# controlled_rectifier2.net
KiCad netlist of a schematic drawn in Altium Designer
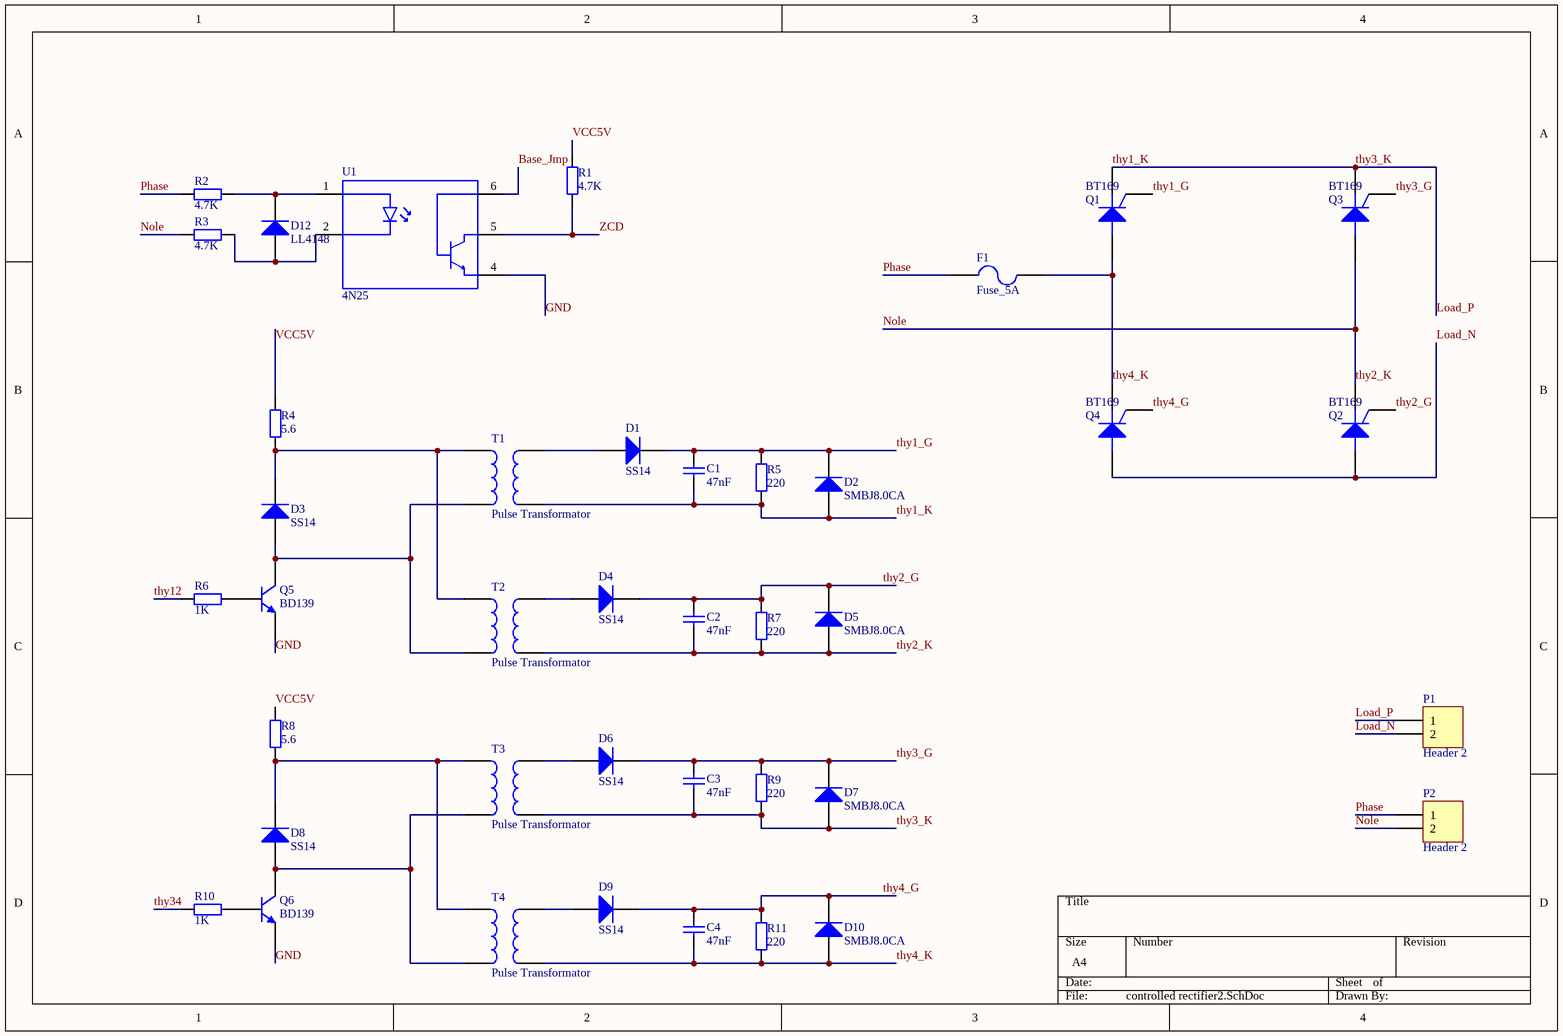
[diagram p0: controlled rectifier2.SchDoc]

(export (version "E")
  (design (tool "Eeschema 10.0.6"))
  (components
    (comp (ref "C1")
      (value "47nF")
      (footprint "CAPS_0805")
      (description "CAP 0805")
      (fields (field (name "DESIGNER") "Abbas Basereh"))
      (libsource (lib "2016AbbasBasereh9365731239-12-10-95_-275613969") (part "CAP SMD 0805"))
    )
    (comp (ref "C2")
      (value "47nF")
      (footprint "CAPS_0805")
      (description "CAP 0805")
      (fields (field (name "DESIGNER") "Abbas Basereh"))
      (libsource (lib "2016AbbasBasereh9365731239-12-10-95_-275613969") (part "CAP SMD 0805"))
    )
    (comp (ref "C3")
      (value "47nF")
      (footprint "CAPS_0805")
      (description "CAP 0805")
      (fields (field (name "DESIGNER") "Abbas Basereh"))
      (libsource (lib "2016AbbasBasereh9365731239-12-10-95_-275613969") (part "CAP SMD 0805"))
    )
    (comp (ref "C4")
      (value "47nF")
      (footprint "CAPS_0805")
      (description "CAP 0805")
      (fields (field (name "DESIGNER") "Abbas Basereh"))
      (libsource (lib "2016AbbasBasereh9365731239-12-10-95_-275613969") (part "CAP SMD 0805"))
    )
    (comp (ref "D1")
      (value "SS14")
      (footprint "DO-214AC")
      (description "Default Diode")
      (fields (field (name "PUBLISHER") "Altium Limited"))
      (libsource (lib "Miscellaneous Devices") (part "Diode"))
    )
    (comp (ref "D2")
      (value "SMBJ8.0CA")
      (footprint "SMC")
      (description "Default Diode")
      (fields (field (name "PUBLISHER") "Altium Limited"))
      (libsource (lib "Miscellaneous Devices") (part "Diode"))
    )
    (comp (ref "D3")
      (value "SS14")
      (footprint "DO-214AC")
      (description "Default Diode")
      (fields (field (name "PUBLISHER") "Altium Limited"))
      (libsource (lib "Miscellaneous Devices") (part "Diode"))
    )
    (comp (ref "D4")
      (value "SS14")
      (footprint "DO-214AC")
      (description "Default Diode")
      (fields (field (name "PUBLISHER") "Altium Limited"))
      (libsource (lib "Miscellaneous Devices") (part "Diode"))
    )
    (comp (ref "D5")
      (value "SMBJ8.0CA")
      (footprint "SMC")
      (description "Default Diode")
      (fields (field (name "PUBLISHER") "Altium Limited"))
      (libsource (lib "Miscellaneous Devices") (part "Diode"))
    )
    (comp (ref "D6")
      (value "SS14")
      (footprint "DO-214AC")
      (description "Default Diode")
      (fields (field (name "PUBLISHER") "Altium Limited"))
      (libsource (lib "Miscellaneous Devices") (part "Diode"))
    )
    (comp (ref "D7")
      (value "SMBJ8.0CA")
      (footprint "SMC")
      (description "Default Diode")
      (fields (field (name "PUBLISHER") "Altium Limited"))
      (libsource (lib "Miscellaneous Devices") (part "Diode"))
    )
    (comp (ref "D8")
      (value "SS14")
      (footprint "DO-214AC")
      (description "Default Diode")
      (fields (field (name "PUBLISHER") "Altium Limited"))
      (libsource (lib "Miscellaneous Devices") (part "Diode"))
    )
    (comp (ref "D9")
      (value "SS14")
      (footprint "DO-214AC")
      (description "Default Diode")
      (fields (field (name "PUBLISHER") "Altium Limited"))
      (libsource (lib "Miscellaneous Devices") (part "Diode"))
    )
    (comp (ref "D10")
      (value "SMBJ8.0CA")
      (footprint "SMC")
      (description "Default Diode")
      (fields (field (name "PUBLISHER") "Altium Limited"))
      (libsource (lib "Miscellaneous Devices") (part "Diode"))
    )
    (comp (ref "D12")
      (value "LL4148")
      (footprint "SOD80, LL-34")
      (description "Default Diode")
      (fields (field (name "PUBLISHER") "Altium Limited"))
      (libsource (lib "Miscellaneous Devices") (part "Diode"))
    )
    (comp (ref "F1")
      (value "Fuse_5A")
      (footprint "fuse-2")
      (description "Fuse")
      (fields (field (name "PUBLISHER") "Altium Limited"))
      (libsource (lib "Miscellaneous Devices") (part "Fuse 2"))
    )
    (comp (ref "P1")
      (value "Header 2")
      (footprint "Phoenix 2 Pin -RA")
      (description "Header, 2-Pin")
      (fields (field (name "PUBLISHER") "Altium Limited"))
      (libsource (lib "Miscellaneous Connectors") (part "Header 2"))
    )
    (comp (ref "P2")
      (value "Header 2")
      (footprint "Phoenix 2 Pin -RA")
      (description "Header, 2-Pin")
      (fields (field (name "PUBLISHER") "Altium Limited"))
      (libsource (lib "Miscellaneous Connectors") (part "Header 2"))
    )
    (comp (ref "Q1")
      (value "BT169")
      (footprint "BT169")
      (description "Silicon Controlled Rectifier")
      (fields (field (name "PUBLISHER") "Altium Limited"))
      (libsource (lib "Miscellaneous Devices") (part "SCR"))
    )
    (comp (ref "Q2")
      (value "BT169")
      (footprint "BT169")
      (description "Silicon Controlled Rectifier")
      (fields (field (name "PUBLISHER") "Altium Limited"))
      (libsource (lib "Miscellaneous Devices") (part "SCR"))
    )
    (comp (ref "Q3")
      (value "BT169")
      (footprint "BT169")
      (description "Silicon Controlled Rectifier")
      (fields (field (name "PUBLISHER") "Altium Limited"))
      (libsource (lib "Miscellaneous Devices") (part "SCR"))
    )
    (comp (ref "Q4")
      (value "BT169")
      (footprint "BT169")
      (description "Silicon Controlled Rectifier")
      (fields (field (name "PUBLISHER") "Altium Limited"))
      (libsource (lib "Miscellaneous Devices") (part "SCR"))
    )
    (comp (ref "Q5")
      (value "BD139")
      (footprint "BD139")
      (description "NPN Bipolar Transistor")
      (fields (field (name "PUBLISHER") "Altium Limited"))
      (libsource (lib "Miscellaneous Devices") (part "NPN"))
    )
    (comp (ref "Q6")
      (value "BD139")
      (footprint "BD139")
      (description "NPN Bipolar Transistor")
      (fields (field (name "PUBLISHER") "Altium Limited"))
      (libsource (lib "Miscellaneous Devices") (part "NPN"))
    )
    (comp (ref "R1")
      (value "4.7K")
      (footprint "res_0805")
      (description "Resistor")
      (fields (field (name "PUBLISHER") "Altium Limited"))
      (libsource (lib "") (part "Res2_1"))
    )
    (comp (ref "R2")
      (value "4.7K")
      (footprint "res_0805")
      (description "Resistor")
      (fields (field (name "PUBLISHER") "Altium Limited"))
      (libsource (lib "Miscellaneous Devices") (part "Res2"))
    )
    (comp (ref "R3")
      (value "4.7K")
      (footprint "res_0805")
      (description "Resistor")
      (fields (field (name "PUBLISHER") "Altium Limited"))
      (libsource (lib "Miscellaneous Devices") (part "Res2"))
    )
    (comp (ref "R4")
      (value "5.6")
      (footprint "res_0805")
      (description "Resistor")
      (fields (field (name "PUBLISHER") "Altium Limited"))
      (libsource (lib "") (part "Res2_1"))
    )
    (comp (ref "R5")
      (value "220")
      (footprint "res_0805")
      (description "Resistor")
      (fields (field (name "PUBLISHER") "Altium Limited"))
      (libsource (lib "") (part "Res2_1"))
    )
    (comp (ref "R6")
      (value "1K")
      (footprint "res_0805")
      (description "Resistor")
      (fields (field (name "PUBLISHER") "Altium Limited"))
      (libsource (lib "Miscellaneous Devices") (part "Res2"))
    )
    (comp (ref "R7")
      (value "220")
      (footprint "res_0805")
      (description "Resistor")
      (fields (field (name "PUBLISHER") "Altium Limited"))
      (libsource (lib "") (part "Res2_1"))
    )
    (comp (ref "R8")
      (value "5.6")
      (footprint "res_0805")
      (description "Resistor")
      (fields (field (name "PUBLISHER") "Altium Limited"))
      (libsource (lib "") (part "Res2_1"))
    )
    (comp (ref "R9")
      (value "220")
      (footprint "res_0805")
      (description "Resistor")
      (fields (field (name "PUBLISHER") "Altium Limited"))
      (libsource (lib "") (part "Res2_1"))
    )
    (comp (ref "R10")
      (value "1K")
      (footprint "res_0805")
      (description "Resistor")
      (fields (field (name "PUBLISHER") "Altium Limited"))
      (libsource (lib "Miscellaneous Devices") (part "Res2"))
    )
    (comp (ref "R11")
      (value "220")
      (footprint "res_0805")
      (description "Resistor")
      (fields (field (name "PUBLISHER") "Altium Limited"))
      (libsource (lib "") (part "Res2_1"))
    )
    (comp (ref "T1")
      (value "Pulse Transformator")
      (footprint "Pulse Trans_Small")
      (description "Transformer")
      (fields (field (name "PUBLISHER") "Altium Limited"))
      (libsource (lib "Miscellaneous Devices") (part "Trans"))
    )
    (comp (ref "T2")
      (value "Pulse Transformator")
      (footprint "Pulse Trans_Small")
      (description "Transformer")
      (fields (field (name "PUBLISHER") "Altium Limited"))
      (libsource (lib "Miscellaneous Devices") (part "Trans"))
    )
    (comp (ref "T3")
      (value "Pulse Transformator")
      (footprint "Pulse Trans_Small")
      (description "Transformer")
      (fields (field (name "PUBLISHER") "Altium Limited"))
      (libsource (lib "Miscellaneous Devices") (part "Trans"))
    )
    (comp (ref "T4")
      (value "Pulse Transformator")
      (footprint "Pulse Trans_Small")
      (description "Transformer")
      (fields (field (name "PUBLISHER") "Altium Limited"))
      (libsource (lib "Miscellaneous Devices") (part "Trans"))
    )
    (comp (ref "U1")
      (value "4N25")
      (footprint "DIP762W50P254L712H400Q6N")
      (description "Optoisolator Transistor with Base Output 5000Vrms 1 Channel 6-DIP")
      (fields (field (name "MF") "Vishay Semiconductor"))
      (libsource (lib "altium-import") (part "root_0_4N25_"))
    )
  )
  (nets
    (net (code "1") (name "/Base_Jmp") (class "Default")
      (node (ref "U1") (pin "6") (pinfunction "B_6") (pintype "passive"))
    )
    (net (code "2") (name "/GND") (class "Default")
      (node (ref "Q5") (pin "3") (pinfunction "E_3") (pintype "passive"))
      (node (ref "Q6") (pin "3") (pinfunction "E_3") (pintype "passive"))
      (node (ref "U1") (pin "4") (pinfunction "E_4") (pintype "passive"))
    )
    (net (code "3") (name "/Load_N") (class "Default")
      (node (ref "P1") (pin "2") (pinfunction "2_2") (pintype "passive"))
      (node (ref "Q2") (pin "1") (pinfunction "A_1") (pintype "passive"))
      (node (ref "Q4") (pin "1") (pinfunction "A_1") (pintype "passive"))
    )
    (net (code "4") (name "/Load_P") (class "Default")
      (node (ref "C1") (pin "1") (pinfunction "1_1") (pintype "passive"))
      (node (ref "C3") (pin "1") (pinfunction "1_1") (pintype "passive"))
      (node (ref "D2") (pin "1") (pinfunction "A_1") (pintype "passive"))
      (node (ref "D7") (pin "1") (pinfunction "A_1") (pintype "passive"))
      (node (ref "P1") (pin "1") (pinfunction "1_1") (pintype "passive"))
      (node (ref "Q1") (pin "3") (pinfunction "K_3") (pintype "passive"))
      (node (ref "Q3") (pin "3") (pinfunction "K_3") (pintype "passive"))
      (node (ref "R5") (pin "1") (pinfunction "1_1") (pintype "passive"))
      (node (ref "R9") (pin "1") (pinfunction "1_1") (pintype "passive"))
      (node (ref "T1") (pin "4") (pinfunction "4_4") (pintype "passive"))
      (node (ref "T3") (pin "4") (pinfunction "4_4") (pintype "passive"))
    )
    (net (code "5") (name "/Nole") (class "Default")
      (node (ref "C2") (pin "1") (pinfunction "1_1") (pintype "passive"))
      (node (ref "D5") (pin "1") (pinfunction "A_1") (pintype "passive"))
      (node (ref "P2") (pin "2") (pinfunction "2_2") (pintype "passive"))
      (node (ref "Q2") (pin "3") (pinfunction "K_3") (pintype "passive"))
      (node (ref "Q3") (pin "1") (pinfunction "A_1") (pintype "passive"))
      (node (ref "R3") (pin "1") (pinfunction "1_1") (pintype "passive"))
      (node (ref "R7") (pin "1") (pinfunction "1_1") (pintype "passive"))
      (node (ref "T2") (pin "4") (pinfunction "4_4") (pintype "passive"))
    )
    (net (code "6") (name "/Phase") (class "Default")
      (node (ref "F1") (pin "1") (pinfunction "1_1") (pintype "passive"))
      (node (ref "P2") (pin "1") (pinfunction "1_1") (pintype "passive"))
      (node (ref "R2") (pin "1") (pinfunction "1_1") (pintype "passive"))
    )
    (net (code "7") (name "/VCC5V") (class "Default")
      (node (ref "R1") (pin "2") (pinfunction "2_2") (pintype "passive"))
      (node (ref "R4") (pin "2") (pinfunction "2_2") (pintype "passive"))
      (node (ref "R8") (pin "2") (pinfunction "2_2") (pintype "passive"))
    )
    (net (code "8") (name "/ZCD") (class "Default")
      (node (ref "R1") (pin "1") (pinfunction "1_1") (pintype "passive"))
      (node (ref "U1") (pin "5") (pinfunction "C_5") (pintype "passive"))
    )
    (net (code "9") (name "/thy1_G") (class "Default")
      (node (ref "C1") (pin "2") (pinfunction "2_2") (pintype "passive"))
      (node (ref "D1") (pin "2") (pinfunction "K_2") (pintype "passive"))
      (node (ref "D2") (pin "2") (pinfunction "K_2") (pintype "passive"))
      (node (ref "Q1") (pin "2") (pinfunction "G_2") (pintype "passive"))
      (node (ref "R5") (pin "2") (pinfunction "2_2") (pintype "passive"))
    )
    (net (code "10") (name "/thy2_G") (class "Default")
      (node (ref "C2") (pin "2") (pinfunction "2_2") (pintype "passive"))
      (node (ref "D4") (pin "2") (pinfunction "K_2") (pintype "passive"))
      (node (ref "D5") (pin "2") (pinfunction "K_2") (pintype "passive"))
      (node (ref "Q2") (pin "2") (pinfunction "G_2") (pintype "passive"))
      (node (ref "R7") (pin "2") (pinfunction "2_2") (pintype "passive"))
    )
    (net (code "11") (name "/thy3_G") (class "Default")
      (node (ref "C3") (pin "2") (pinfunction "2_2") (pintype "passive"))
      (node (ref "D6") (pin "2") (pinfunction "K_2") (pintype "passive"))
      (node (ref "D7") (pin "2") (pinfunction "K_2") (pintype "passive"))
      (node (ref "Q3") (pin "2") (pinfunction "G_2") (pintype "passive"))
      (node (ref "R9") (pin "2") (pinfunction "2_2") (pintype "passive"))
    )
    (net (code "12") (name "/thy4_G") (class "Default")
      (node (ref "C4") (pin "2") (pinfunction "2_2") (pintype "passive"))
      (node (ref "D10") (pin "2") (pinfunction "K_2") (pintype "passive"))
      (node (ref "D9") (pin "2") (pinfunction "K_2") (pintype "passive"))
      (node (ref "Q4") (pin "2") (pinfunction "G_2") (pintype "passive"))
      (node (ref "R11") (pin "2") (pinfunction "2_2") (pintype "passive"))
    )
    (net (code "13") (name "/thy4_K") (class "Default")
      (node (ref "C4") (pin "1") (pinfunction "1_1") (pintype "passive"))
      (node (ref "D10") (pin "1") (pinfunction "A_1") (pintype "passive"))
      (node (ref "F1") (pin "2") (pinfunction "2_2") (pintype "passive"))
      (node (ref "Q1") (pin "1") (pinfunction "A_1") (pintype "passive"))
      (node (ref "Q4") (pin "3") (pinfunction "K_3") (pintype "passive"))
      (node (ref "R11") (pin "1") (pinfunction "1_1") (pintype "passive"))
      (node (ref "T4") (pin "4") (pinfunction "4_4") (pintype "passive"))
    )
    (net (code "14") (name "/thy12") (class "Default")
      (node (ref "R6") (pin "1") (pinfunction "1_1") (pintype "passive"))
    )
    (net (code "15") (name "/thy34") (class "Default")
      (node (ref "R10") (pin "1") (pinfunction "1_1") (pintype "passive"))
    )
    (net (code "16") (name "Net-(D1-A)") (class "Default")
      (node (ref "D1") (pin "1") (pinfunction "A_1") (pintype "passive"))
      (node (ref "T1") (pin "3") (pinfunction "3_3") (pintype "passive"))
    )
    (net (code "17") (name "Net-(D3-A)") (class "Default")
      (node (ref "D3") (pin "1") (pinfunction "A_1") (pintype "passive"))
      (node (ref "Q5") (pin "1") (pinfunction "C_1") (pintype "passive"))
      (node (ref "T1") (pin "2") (pinfunction "2_2") (pintype "passive"))
      (node (ref "T2") (pin "2") (pinfunction "2_2") (pintype "passive"))
    )
    (net (code "18") (name "Net-(D3-K)") (class "Default")
      (node (ref "D3") (pin "2") (pinfunction "K_2") (pintype "passive"))
      (node (ref "R4") (pin "1") (pinfunction "1_1") (pintype "passive"))
      (node (ref "T1") (pin "1") (pinfunction "1_1") (pintype "passive"))
      (node (ref "T2") (pin "1") (pinfunction "1_1") (pintype "passive"))
    )
    (net (code "19") (name "Net-(D4-A)") (class "Default")
      (node (ref "D4") (pin "1") (pinfunction "A_1") (pintype "passive"))
      (node (ref "T2") (pin "3") (pinfunction "3_3") (pintype "passive"))
    )
    (net (code "20") (name "Net-(D6-A)") (class "Default")
      (node (ref "D6") (pin "1") (pinfunction "A_1") (pintype "passive"))
      (node (ref "T3") (pin "3") (pinfunction "3_3") (pintype "passive"))
    )
    (net (code "21") (name "Net-(D8-A)") (class "Default")
      (node (ref "D8") (pin "1") (pinfunction "A_1") (pintype "passive"))
      (node (ref "Q6") (pin "1") (pinfunction "C_1") (pintype "passive"))
      (node (ref "T3") (pin "2") (pinfunction "2_2") (pintype "passive"))
      (node (ref "T4") (pin "2") (pinfunction "2_2") (pintype "passive"))
    )
    (net (code "22") (name "Net-(D8-K)") (class "Default")
      (node (ref "D8") (pin "2") (pinfunction "K_2") (pintype "passive"))
      (node (ref "R8") (pin "1") (pinfunction "1_1") (pintype "passive"))
      (node (ref "T3") (pin "1") (pinfunction "1_1") (pintype "passive"))
      (node (ref "T4") (pin "1") (pinfunction "1_1") (pintype "passive"))
    )
    (net (code "23") (name "Net-(D9-A)") (class "Default")
      (node (ref "D9") (pin "1") (pinfunction "A_1") (pintype "passive"))
      (node (ref "T4") (pin "3") (pinfunction "3_3") (pintype "passive"))
    )
    (net (code "24") (name "Net-(D12-A)") (class "Default")
      (node (ref "D12") (pin "1") (pinfunction "A_1") (pintype "passive"))
      (node (ref "R3") (pin "2") (pinfunction "2_2") (pintype "passive"))
      (node (ref "U1") (pin "2") (pinfunction "K_2") (pintype "passive"))
    )
    (net (code "25") (name "Net-(D12-K)") (class "Default")
      (node (ref "D12") (pin "2") (pinfunction "K_2") (pintype "passive"))
      (node (ref "R2") (pin "2") (pinfunction "2_2") (pintype "passive"))
      (node (ref "U1") (pin "1") (pinfunction "A_1") (pintype "passive"))
    )
    (net (code "26") (name "Net-(Q5-B)") (class "Default")
      (node (ref "Q5") (pin "2") (pinfunction "B_2") (pintype "passive"))
      (node (ref "R6") (pin "2") (pinfunction "2_2") (pintype "passive"))
    )
    (net (code "27") (name "Net-(Q6-B)") (class "Default")
      (node (ref "Q6") (pin "2") (pinfunction "B_2") (pintype "passive"))
      (node (ref "R10") (pin "2") (pinfunction "2_2") (pintype "passive"))
    )
  )
)
